# Power.net
KiCad netlist of a schematic drawn in Altium Designer
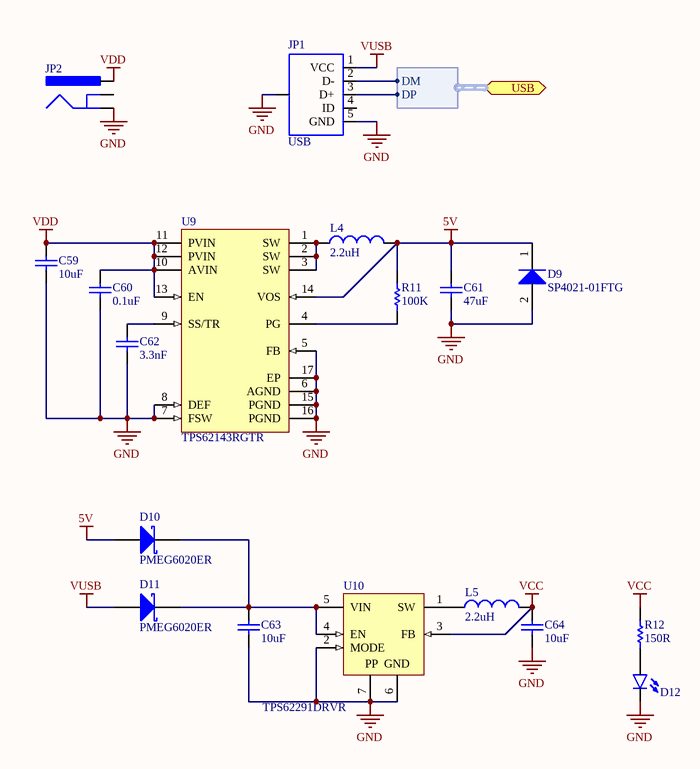
[diagram p0: Power.SchDoc]

(export (version "E")
  (design (tool "Eeschema 10.0.6"))
  (components
    (comp (ref "C59")
      (value "10uF")
      (footprint "C1206[3216X160]")
      (description "10uF 50V 20% 1206 (3216 Metric)")
      (fields (field (name "TOLERANCE") "20%") (field (name "PARTNUMBER") "UMK316BBJ106ML-T"))
      (libsource (lib "Capacitors") (part "CAP_10uF_50V_1206_20%"))
    )
    (comp (ref "C60")
      (value "0.1uF")
      (footprint "C0402[1005X55]")
      (description "0.1uF 100V 10% 0402 (1005 Metric)")
      (fields (field (name "TOLERANCE") "10%") (field (name "PARTNUMBER") "GRM155R62A104KE14D"))
      (libsource (lib "Capacitors") (part "CAP_0.1uF_100V_0402_10%"))
    )
    (comp (ref "C61")
      (value "47uF")
      (footprint "C1210[3225X250]")
      (description "47uF 6.3V 10% 1210 (3225 Metric)")
      (fields (field (name "TOLERANCE") "10%") (field (name "PARTNUMBER") "GRM32ER70J476KE20L"))
      (libsource (lib "Capacitors") (part "CAP_47uF_6.3V_1210_10%"))
    )
    (comp (ref "C62")
      (value "3.3nF")
      (footprint "C0402[1005X55]")
      (description "3.3nF 50V 10% 0402 (1005 Metric)")
      (fields (field (name "TOLERANCE") "10%") (field (name "PARTNUMBER") "GRM155R71H332KA01D"))
      (libsource (lib "Capacitors") (part "CAP_3.3nF_50V_0402_10%"))
    )
    (comp (ref "C63")
      (value "10uF")
      (footprint "C0402[1005X55]")
      (description "10uF 6.3V 20% 0402 (1005 Metric)")
      (fields (field (name "TOLERANCE") "20%") (field (name "PARTNUMBER") "GRM155R60J106ME44D"))
      (libsource (lib "Capacitors") (part "CAP_10uF_6.3V_0402_20%"))
    )
    (comp (ref "C64")
      (value "10uF")
      (footprint "C0402[1005X55]")
      (description "10uF 6.3V 20% 0402 (1005 Metric)")
      (fields (field (name "TOLERANCE") "20%") (field (name "PARTNUMBER") "GRM155R60J106ME44D"))
      (libsource (lib "Capacitors") (part "CAP_10uF_6.3V_0402_20%"))
    )
    (comp (ref "D9")
      (value "SP4021-01FTG")
      (footprint "SOD-323")
      (fields (field (name "MANUFACTURER") "Littelfuse"))
      (libsource (lib "Diodes") (part "SP4021-01FTG"))
    )
    (comp (ref "D10")
      (value "PMEG6020ER")
      (footprint "SOD-123")
      (fields (field (name "PARTNUMBER") "PMEG6020ER,115") (field (name "MANUFACTURER") "NXP Semiconductors"))
      (libsource (lib "Diodes") (part "PMEG6020ER"))
    )
    (comp (ref "D11")
      (value "PMEG6020ER")
      (footprint "SOD-123")
      (fields (field (name "PARTNUMBER") "PMEG6020ER,115") (field (name "MANUFACTURER") "NXP Semiconductors"))
      (libsource (lib "Diodes") (part "PMEG6020ER"))
    )
    (comp (ref "D12")
      (value "LED_0603_GREEN_5mA")
      (footprint "LED0603")
      (fields (field (name "PARTNUMBER") "LTST-C193TGKT-5A") (field (name "MANUFACTURER") "Lite-On Inc."))
      (libsource (lib "LEDs") (part "LED_0603_GREEN_5mA"))
    )
    (comp (ref "JP1")
      (value "USB")
      (footprint "USB-MICROB")
      (fields (field (name "PARTNUMBER") "10118192-0001LF") (field (name "MANUFACTURER") "Amphenol FCI"))
      (libsource (lib "Connectors") (part "USB_MICROB_SMT"))
    )
    (comp (ref "JP2")
      (value "~")
      (footprint "POWER_JACK_SMD")
      (libsource (lib "Components") (part "POWER_JACK"))
    )
    (comp (ref "L4")
      (value "2.2uH")
      (footprint "IND0805")
      (description "2.2uH 20% 1.7A 0805")
      (fields (field (name "PARTNUMBER") "LQM21PN2R2MGHL") (field (name "MANUFACTURER") "Murata"))
      (libsource (lib "Inductors") (part "IND_2.2uH_1.7A_0805_20%"))
    )
    (comp (ref "L5")
      (value "2.2uH")
      (footprint "IND0805")
      (description "2.2uH 20% 1.7A 0805")
      (fields (field (name "PARTNUMBER") "LQM21PN2R2MGHL") (field (name "MANUFACTURER") "Murata"))
      (libsource (lib "Inductors") (part "IND_2.2uH_1.7A_0805_20%"))
    )
    (comp (ref "R11")
      (value "100K")
      (footprint "R0402[1005]")
      (description "100K 0.063W 1% 0402 (1005 Metric)")
      (fields (field (name "MANUFACTURER") "KOA Speer") (field (name "PARTNUMBER") "RK73H1ETTP1003F"))
      (libsource (lib "Resistors") (part "RES_100K_0402_1%"))
    )
    (comp (ref "R12")
      (value "150R")
      (footprint "R0402[1005]")
      (description "150R 0.063W 1% 0402 (1005 Metric)")
      (fields (field (name "POWER") "0.063W") (field (name "TOLERANCE") "1%"))
      (libsource (lib "Resistors") (part "RES_150R_0402_1%"))
    )
    (comp (ref "U9")
      (value "TPS62143RGTR")
      (footprint "RGT0016C_V")
      (fields (field (name "MANUFACTURER") "Texas Instruments"))
      (libsource (lib "Altium Content Vault") (part "TI-TPS62133RGT16-1700X1700TP"))
    )
    (comp (ref "U10")
      (value "TPS62291DRVR")
      (footprint "WSON-6")
      (description "Voltage Regulators - Switching Regulators 2.25MHz 1A Step-Down Cnvrtr 3.3V Output")
      (fields (field (name "MANUFACTURER") "Texas Instruments"))
      (libsource (lib "ICs") (part "TPS62291DRVR"))
    )
  )
  (nets
    (net (code "2") (name "/DM") (class "Default")
      (node (ref "JP1") (pin "2") (pinfunction "D-_2") (pintype "passive"))
    )
    (net (code "3") (name "/DP") (class "Default")
      (node (ref "JP1") (pin "3") (pinfunction "D+_3") (pintype "passive"))
    )
    (net (code "5") (name "5V") (class "Default")
      (node (ref "C61") (pin "2") (pinfunction "2_2") (pintype "passive"))
      (node (ref "D10") (pin "2") (pinfunction "A_2") (pintype "passive"))
      (node (ref "D9") (pin "1") (pinfunction "K_1") (pintype "passive"))
      (node (ref "L4") (pin "2") (pinfunction "2_2") (pintype "passive"))
      (node (ref "R11") (pin "2") (pinfunction "2_2") (pintype "passive"))
      (node (ref "U9") (pin "14") (pinfunction "VOS_14") (pintype "input"))
    )
    (net (code "6") (name "GND") (class "Default")
      (node (ref "C59") (pin "1") (pinfunction "1_1") (pintype "passive"))
      (node (ref "C60") (pin "1") (pinfunction "1_1") (pintype "passive"))
      (node (ref "C61") (pin "1") (pinfunction "1_1") (pintype "passive"))
      (node (ref "C62") (pin "1") (pinfunction "1_1") (pintype "passive"))
      (node (ref "C63") (pin "1") (pinfunction "1_1") (pintype "passive"))
      (node (ref "C64") (pin "1") (pinfunction "1_1") (pintype "passive"))
      (node (ref "D12") (pin "C") (pinfunction "C_C") (pintype "passive"))
      (node (ref "D9") (pin "2") (pinfunction "A_2") (pintype "passive"))
      (node (ref "JP1") (pin "5") (pinfunction "GND_5") (pintype "passive"))
      (node (ref "JP1") (pin "6") (pinfunction "SHIELD_6") (pintype "passive"))
      (node (ref "JP2") (pin "2") (pinfunction "GND_2") (pintype "passive"))
      (node (ref "U10") (pin "2") (pinfunction "MODE_2") (pintype "input"))
      (node (ref "U10") (pin "6") (pinfunction "GND_6") (pintype "power_in"))
      (node (ref "U10") (pin "7") (pinfunction "EP_7") (pintype "passive"))
      (node (ref "U9") (pin "15") (pinfunction "PGND_15") (pintype "power_in"))
      (node (ref "U9") (pin "16") (pinfunction "PGND_16") (pintype "power_in"))
      (node (ref "U9") (pin "17") (pinfunction "EP_17") (pintype "power_in"))
      (node (ref "U9") (pin "5") (pinfunction "FB_5") (pintype "input"))
      (node (ref "U9") (pin "6") (pinfunction "AGND_6") (pintype "power_in"))
      (node (ref "U9") (pin "7") (pinfunction "FSW_7") (pintype "input"))
      (node (ref "U9") (pin "8") (pinfunction "DEF_8") (pintype "input"))
    )
    (net (code "7") (name "Net-(D10-K)") (class "Default")
      (node (ref "C63") (pin "2") (pinfunction "2_2") (pintype "passive"))
      (node (ref "D10") (pin "1") (pinfunction "K_1") (pintype "passive"))
      (node (ref "D11") (pin "1") (pinfunction "K_1") (pintype "passive"))
      (node (ref "U10") (pin "4") (pinfunction "EN_4") (pintype "input"))
      (node (ref "U10") (pin "5") (pinfunction "VIN_5") (pintype "power_in"))
    )
    (net (code "8") (name "Net-(D12-PadA)") (class "Default")
      (node (ref "D12") (pin "A") (pinfunction "A_A") (pintype "passive"))
      (node (ref "R12") (pin "1") (pinfunction "1_1") (pintype "passive"))
    )
    (net (code "9") (name "Net-(L4-Pad1)") (class "Default")
      (node (ref "L4") (pin "1") (pinfunction "1_1") (pintype "passive"))
      (node (ref "U9") (pin "1") (pinfunction "SW_1") (pintype "power_in"))
      (node (ref "U9") (pin "2") (pinfunction "SW_2") (pintype "power_in"))
      (node (ref "U9") (pin "3") (pinfunction "SW_3") (pintype "power_in"))
    )
    (net (code "10") (name "Net-(U9-PG)") (class "Default")
      (node (ref "R11") (pin "1") (pinfunction "1_1") (pintype "passive"))
      (node (ref "U9") (pin "4") (pinfunction "PG_4") (pintype "tri_state"))
    )
    (net (code "11") (name "Net-(U9-SS{slash}TR)") (class "Default")
      (node (ref "C62") (pin "2") (pinfunction "2_2") (pintype "passive"))
      (node (ref "U9") (pin "9") (pinfunction "SS/TR_9") (pintype "input"))
    )
    (net (code "12") (name "Net-(U10-SW)") (class "Default")
      (node (ref "L5") (pin "1") (pinfunction "1_1") (pintype "passive"))
      (node (ref "U10") (pin "1") (pinfunction "SW_1") (pintype "power_in"))
    )
    (net (code "13") (name "VCC") (class "Default")
      (node (ref "C64") (pin "2") (pinfunction "2_2") (pintype "passive"))
      (node (ref "L5") (pin "2") (pinfunction "2_2") (pintype "passive"))
      (node (ref "R12") (pin "2") (pinfunction "2_2") (pintype "passive"))
      (node (ref "U10") (pin "3") (pinfunction "FB_3") (pintype "input"))
    )
    (net (code "14") (name "VDD") (class "Default")
      (node (ref "C59") (pin "2") (pinfunction "2_2") (pintype "passive"))
      (node (ref "C60") (pin "2") (pinfunction "2_2") (pintype "passive"))
      (node (ref "JP2") (pin "1") (pinfunction "PWR_1") (pintype "passive"))
      (node (ref "U9") (pin "10") (pinfunction "AVIN_10") (pintype "power_in"))
      (node (ref "U9") (pin "11") (pinfunction "PVIN_11") (pintype "power_in"))
      (node (ref "U9") (pin "12") (pinfunction "PVIN_12") (pintype "power_in"))
      (node (ref "U9") (pin "13") (pinfunction "EN_13") (pintype "input"))
    )
    (net (code "15") (name "VUSB") (class "Default")
      (node (ref "D11") (pin "2") (pinfunction "A_2") (pintype "passive"))
      (node (ref "JP1") (pin "1") (pinfunction "VCC_1") (pintype "passive"))
    )
    (net (code "16") (name "unconnected-(JP1-ID-Pad4)") (class "Default")
      (node (ref "JP1") (pin "4") (pinfunction "ID_4") (pintype "passive"))
    )
    (net (code "17") (name "unconnected-(JP2-GND-Pad3)") (class "Default")
      (node (ref "JP2") (pin "3") (pinfunction "GND_3") (pintype "passive"))
    )
  )
)
